# STM32F072_Platform.net
KiCad netlist of a schematic drawn in Altium Designer
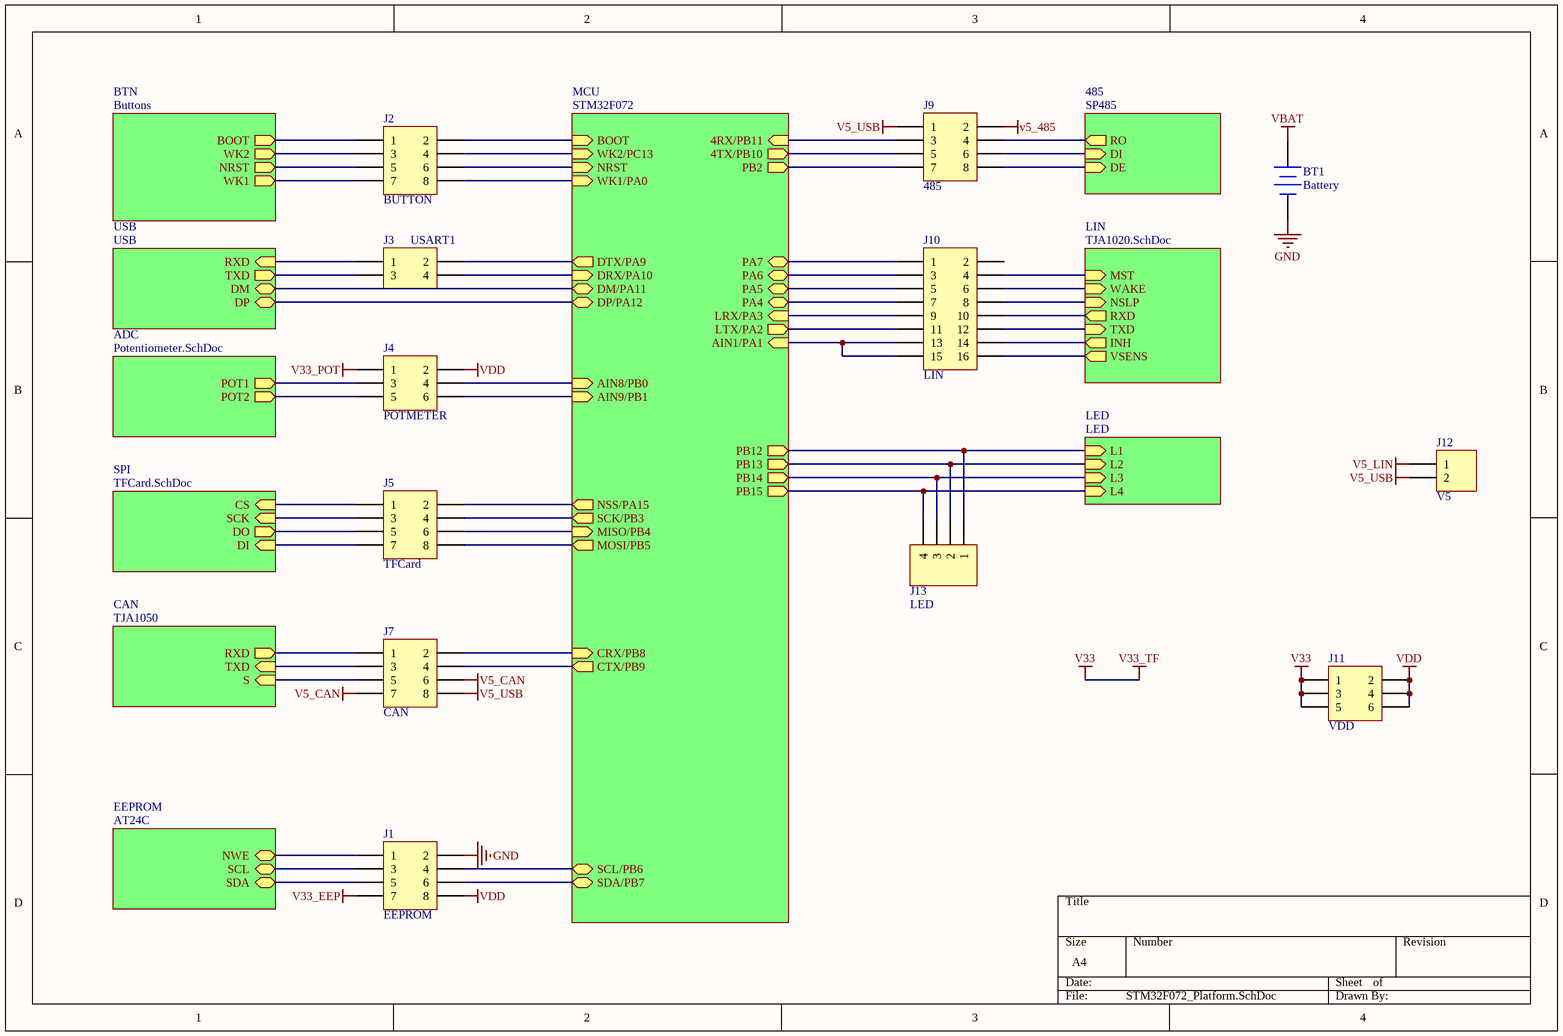
[diagram p0: STM32F072_Platform.SchDoc]

(export (version "E")
  (design (tool "Eeschema 10.0.6"))
  (components
    (comp (ref "BT1")
      (value "Battery")
      (footprint "CR1220")
      (description "Multicell Battery")
      (fields (field (name "PUBLISHER") "Altium Limited"))
      (libsource (lib "Miscellaneous Devices") (part "Battery"))
    )
    (comp (ref "J1")
      (value "EEPROM")
      (footprint "HDR2X4")
      (description "Header, 4-Pin, Dual row")
      (fields (field (name "PUBLISHER") "Altium Limited"))
      (libsource (lib "Miscellaneous Connectors") (part "Header 4X2"))
    )
    (comp (ref "J2")
      (value "BUTTON")
      (footprint "HDR2X4")
      (description "Header, 4-Pin, Dual row")
      (fields (field (name "PUBLISHER") "Altium Limited"))
      (libsource (lib "Miscellaneous Connectors") (part "Header 4X2"))
    )
    (comp (ref "J3")
      (value "USART1")
      (footprint "HDR2X2")
      (description "Header, 2-Pin, Dual row")
      (fields (field (name "PUBLISHER") "Altium Limited"))
      (libsource (lib "Miscellaneous Connectors") (part "Header 2X2"))
    )
    (comp (ref "J4")
      (value "POTMETER")
      (footprint "HDR2X3")
      (description "POT")
      (fields (field (name "PUBLISHER") "Altium Limited"))
      (libsource (lib "Miscellaneous Connectors") (part "Header 3X2"))
    )
    (comp (ref "J5")
      (value "TFCard")
      (footprint "HDR2X4")
      (description "Header, 4-Pin, Dual row")
      (fields (field (name "PUBLISHER") "Altium Limited"))
      (libsource (lib "Miscellaneous Connectors") (part "Header 4X2"))
    )
    (comp (ref "J7")
      (value "CAN")
      (footprint "HDR2X4")
      (description "Header, 4-Pin, Dual row")
      (fields (field (name "PUBLISHER") "Altium Limited"))
      (libsource (lib "Miscellaneous Connectors") (part "Header 4X2"))
    )
    (comp (ref "J9")
      (value "485")
      (footprint "HDR2X4")
      (description "Header, 4-Pin, Dual row")
      (fields (field (name "PUBLISHER") "Altium Limited"))
      (libsource (lib "Miscellaneous Connectors") (part "Header 4X2"))
    )
    (comp (ref "J10")
      (value "LIN")
      (footprint "HDR2X8")
      (description "Header, 8-Pin, Dual row")
      (fields (field (name "PUBLISHER") "Altium Limited"))
      (libsource (lib "Miscellaneous Connectors") (part "Header 8X2"))
    )
    (comp (ref "J11")
      (value "VDD")
      (footprint "HDR2X3")
      (description "Header, 3-Pin, Dual row")
      (fields (field (name "PUBLISHER") "Altium Limited"))
      (libsource (lib "Miscellaneous Connectors") (part "Header 3X2"))
    )
    (comp (ref "J12")
      (value "V5")
      (footprint "HDR1X2")
      (description "Header, 2-Pin")
      (fields (field (name "PUBLISHER") "Altium Limited"))
      (libsource (lib "Miscellaneous Connectors") (part "Header 2"))
    )
    (comp (ref "J13")
      (value "LED")
      (footprint "HDR2X2")
      (description "Header, 4-Pin")
      (fields (field (name "PUBLISHER") "Altium Limited"))
      (libsource (lib "Miscellaneous Connectors") (part "Header 4"))
    )
  )
  (nets
    (net (code "1") (name "/4RX{slash}PB11") (class "Default")
      (node (ref "J9") (pin "3") (pinfunction "3_3") (pintype "passive"))
    )
    (net (code "2") (name "/4TX{slash}PB10") (class "Default")
      (node (ref "J9") (pin "5") (pinfunction "5_5") (pintype "passive"))
    )
    (net (code "3") (name "/AIN1{slash}PA1") (class "Default")
      (node (ref "J10") (pin "13") (pinfunction "13_13") (pintype "passive"))
      (node (ref "J10") (pin "15") (pinfunction "15_15") (pintype "passive"))
    )
    (net (code "4") (name "/AIN8{slash}PB0") (class "Default")
      (node (ref "J4") (pin "4") (pinfunction "4_4") (pintype "passive"))
    )
    (net (code "5") (name "/AIN9{slash}PB1") (class "Default")
      (node (ref "J4") (pin "6") (pinfunction "6_6") (pintype "passive"))
    )
    (net (code "6") (name "/BOOT") (class "Default")
      (node (ref "J2") (pin "2") (pinfunction "2_2") (pintype "passive"))
    )
    (net (code "7") (name "/BOOT_1") (class "Default")
      (node (ref "J2") (pin "1") (pinfunction "1_1") (pintype "passive"))
    )
    (net (code "8") (name "/CRX{slash}PB8") (class "Default")
      (node (ref "J7") (pin "2") (pinfunction "2_2") (pintype "passive"))
    )
    (net (code "9") (name "/CS") (class "Default")
      (node (ref "J5") (pin "1") (pinfunction "1_1") (pintype "passive"))
    )
    (net (code "10") (name "/CTX{slash}PB9") (class "Default")
      (node (ref "J7") (pin "4") (pinfunction "4_4") (pintype "passive"))
    )
    (net (code "11") (name "/DE") (class "Default")
      (node (ref "J9") (pin "8") (pinfunction "8_8") (pintype "passive"))
    )
    (net (code "12") (name "/DI") (class "Default")
      (node (ref "J5") (pin "7") (pinfunction "7_7") (pintype "passive"))
    )
    (net (code "13") (name "/DI_1") (class "Default")
      (node (ref "J9") (pin "6") (pinfunction "6_6") (pintype "passive"))
    )
    (net (code "15") (name "/DO") (class "Default")
      (node (ref "J5") (pin "5") (pinfunction "5_5") (pintype "passive"))
    )
    (net (code "17") (name "/DRX{slash}PA10") (class "Default")
      (node (ref "J3") (pin "4") (pinfunction "4_4") (pintype "passive"))
    )
    (net (code "18") (name "/DTX{slash}PA9") (class "Default")
      (node (ref "J3") (pin "2") (pinfunction "2_2") (pintype "passive"))
    )
    (net (code "19") (name "/INH") (class "Default")
      (node (ref "J10") (pin "14") (pinfunction "14_14") (pintype "passive"))
    )
    (net (code "20") (name "/LRX{slash}PA3") (class "Default")
      (node (ref "J10") (pin "9") (pinfunction "9_9") (pintype "passive"))
    )
    (net (code "21") (name "/LTX{slash}PA2") (class "Default")
      (node (ref "J10") (pin "11") (pinfunction "11_11") (pintype "passive"))
    )
    (net (code "22") (name "/MISO{slash}PB4") (class "Default")
      (node (ref "J5") (pin "6") (pinfunction "6_6") (pintype "passive"))
    )
    (net (code "23") (name "/MOSI{slash}PB5") (class "Default")
      (node (ref "J5") (pin "8") (pinfunction "8_8") (pintype "passive"))
    )
    (net (code "24") (name "/MST") (class "Default")
      (node (ref "J10") (pin "4") (pinfunction "4_4") (pintype "passive"))
    )
    (net (code "25") (name "/NRST") (class "Default")
      (node (ref "J2") (pin "6") (pinfunction "6_6") (pintype "passive"))
    )
    (net (code "26") (name "/NRST_1") (class "Default")
      (node (ref "J2") (pin "5") (pinfunction "5_5") (pintype "passive"))
    )
    (net (code "27") (name "/NSLP") (class "Default")
      (node (ref "J10") (pin "8") (pinfunction "8_8") (pintype "passive"))
    )
    (net (code "28") (name "/NSS{slash}PA15") (class "Default")
      (node (ref "J5") (pin "2") (pinfunction "2_2") (pintype "passive"))
    )
    (net (code "29") (name "/NWE") (class "Default")
      (node (ref "J1") (pin "1") (pinfunction "1_1") (pintype "passive"))
    )
    (net (code "30") (name "/PA4") (class "Default")
      (node (ref "J10") (pin "7") (pinfunction "7_7") (pintype "passive"))
    )
    (net (code "31") (name "/PA5") (class "Default")
      (node (ref "J10") (pin "5") (pinfunction "5_5") (pintype "passive"))
    )
    (net (code "32") (name "/PA6") (class "Default")
      (node (ref "J10") (pin "3") (pinfunction "3_3") (pintype "passive"))
    )
    (net (code "33") (name "/PA7") (class "Default")
      (node (ref "J10") (pin "1") (pinfunction "1_1") (pintype "passive"))
    )
    (net (code "34") (name "/PB2") (class "Default")
      (node (ref "J9") (pin "7") (pinfunction "7_7") (pintype "passive"))
    )
    (net (code "35") (name "/PB12") (class "Default")
      (node (ref "J13") (pin "1") (pinfunction "1_1") (pintype "passive"))
    )
    (net (code "36") (name "/PB13") (class "Default")
      (node (ref "J13") (pin "2") (pinfunction "2_2") (pintype "passive"))
    )
    (net (code "37") (name "/PB14") (class "Default")
      (node (ref "J13") (pin "3") (pinfunction "3_3") (pintype "passive"))
    )
    (net (code "38") (name "/PB15") (class "Default")
      (node (ref "J13") (pin "4") (pinfunction "4_4") (pintype "passive"))
    )
    (net (code "39") (name "/POT1") (class "Default")
      (node (ref "J4") (pin "3") (pinfunction "3_3") (pintype "passive"))
    )
    (net (code "40") (name "/POT2") (class "Default")
      (node (ref "J4") (pin "5") (pinfunction "5_5") (pintype "passive"))
    )
    (net (code "41") (name "/RO") (class "Default")
      (node (ref "J9") (pin "4") (pinfunction "4_4") (pintype "passive"))
    )
    (net (code "42") (name "/RXD") (class "Default")
      (node (ref "J7") (pin "1") (pinfunction "1_1") (pintype "passive"))
    )
    (net (code "43") (name "/RXD_1") (class "Default")
      (node (ref "J3") (pin "1") (pinfunction "1_1") (pintype "passive"))
    )
    (net (code "44") (name "/RXD_2") (class "Default")
      (node (ref "J10") (pin "10") (pinfunction "10_10") (pintype "passive"))
    )
    (net (code "45") (name "/S") (class "Default")
      (node (ref "J7") (pin "5") (pinfunction "5_5") (pintype "passive"))
    )
    (net (code "46") (name "/SCK") (class "Default")
      (node (ref "J5") (pin "3") (pinfunction "3_3") (pintype "passive"))
    )
    (net (code "47") (name "/SCK{slash}PB3") (class "Default")
      (node (ref "J5") (pin "4") (pinfunction "4_4") (pintype "passive"))
    )
    (net (code "48") (name "/SCL") (class "Default")
      (node (ref "J1") (pin "3") (pinfunction "3_3") (pintype "passive"))
    )
    (net (code "49") (name "/SCL{slash}PB6") (class "Default")
      (node (ref "J1") (pin "4") (pinfunction "4_4") (pintype "passive"))
    )
    (net (code "50") (name "/SDA") (class "Default")
      (node (ref "J1") (pin "5") (pinfunction "5_5") (pintype "passive"))
    )
    (net (code "51") (name "/SDA{slash}PB7") (class "Default")
      (node (ref "J1") (pin "6") (pinfunction "6_6") (pintype "passive"))
    )
    (net (code "52") (name "/TXD") (class "Default")
      (node (ref "J7") (pin "3") (pinfunction "3_3") (pintype "passive"))
    )
    (net (code "53") (name "/TXD_1") (class "Default")
      (node (ref "J3") (pin "3") (pinfunction "3_3") (pintype "passive"))
    )
    (net (code "54") (name "/TXD_2") (class "Default")
      (node (ref "J10") (pin "12") (pinfunction "12_12") (pintype "passive"))
    )
    (net (code "55") (name "/VSENS") (class "Default")
      (node (ref "J10") (pin "16") (pinfunction "16_16") (pintype "passive"))
    )
    (net (code "56") (name "/WAKE") (class "Default")
      (node (ref "J10") (pin "6") (pinfunction "6_6") (pintype "passive"))
    )
    (net (code "57") (name "/WK1") (class "Default")
      (node (ref "J2") (pin "7") (pinfunction "7_7") (pintype "passive"))
    )
    (net (code "58") (name "/WK1{slash}PA0") (class "Default")
      (node (ref "J2") (pin "8") (pinfunction "8_8") (pintype "passive"))
    )
    (net (code "59") (name "/WK2") (class "Default")
      (node (ref "J2") (pin "3") (pinfunction "3_3") (pintype "passive"))
    )
    (net (code "60") (name "/WK2{slash}PC13") (class "Default")
      (node (ref "J2") (pin "4") (pinfunction "4_4") (pintype "passive"))
    )
    (net (code "61") (name "GND") (class "Default")
      (node (ref "BT1") (pin "2") (pinfunction "-_2") (pintype "passive"))
      (node (ref "J1") (pin "2") (pinfunction "2_2") (pintype "passive"))
    )
    (net (code "62") (name "V5_CAN") (class "Default")
      (node (ref "J7") (pin "6") (pinfunction "6_6") (pintype "passive"))
      (node (ref "J7") (pin "7") (pinfunction "7_7") (pintype "passive"))
    )
    (net (code "63") (name "V5_LIN") (class "Default")
      (node (ref "J12") (pin "1") (pinfunction "1_1") (pintype "passive"))
    )
    (net (code "64") (name "V5_USB") (class "Default")
      (node (ref "J12") (pin "2") (pinfunction "2_2") (pintype "passive"))
      (node (ref "J7") (pin "8") (pinfunction "8_8") (pintype "passive"))
      (node (ref "J9") (pin "1") (pinfunction "1_1") (pintype "passive"))
    )
    (net (code "65") (name "V33") (class "Default")
      (node (ref "J11") (pin "1") (pinfunction "1_1") (pintype "passive"))
      (node (ref "J11") (pin "3") (pinfunction "3_3") (pintype "passive"))
      (node (ref "J11") (pin "5") (pinfunction "5_5") (pintype "passive"))
    )
    (net (code "66") (name "V33_EEP") (class "Default")
      (node (ref "J1") (pin "7") (pinfunction "7_7") (pintype "passive"))
    )
    (net (code "67") (name "V33_POT") (class "Default")
      (node (ref "J4") (pin "1") (pinfunction "1_1") (pintype "passive"))
    )
    (net (code "68") (name "VBAT") (class "Default")
      (node (ref "BT1") (pin "1") (pinfunction "+_1") (pintype "passive"))
    )
    (net (code "69") (name "VDD") (class "Default")
      (node (ref "J1") (pin "8") (pinfunction "8_8") (pintype "passive"))
      (node (ref "J11") (pin "2") (pinfunction "2_2") (pintype "passive"))
      (node (ref "J11") (pin "4") (pinfunction "4_4") (pintype "passive"))
      (node (ref "J11") (pin "6") (pinfunction "6_6") (pintype "passive"))
      (node (ref "J4") (pin "2") (pinfunction "2_2") (pintype "passive"))
    )
    (net (code "70") (name "unconnected-(J10-Pad2)") (class "Default")
      (node (ref "J10") (pin "2") (pinfunction "2_2") (pintype "passive"))
    )
    (net (code "71") (name "v5_485") (class "Default")
      (node (ref "J9") (pin "2") (pinfunction "2_2") (pintype "passive"))
    )
  )
)
